# AND_4x4.net
KiCad netlist of a schematic drawn in Altium Designer
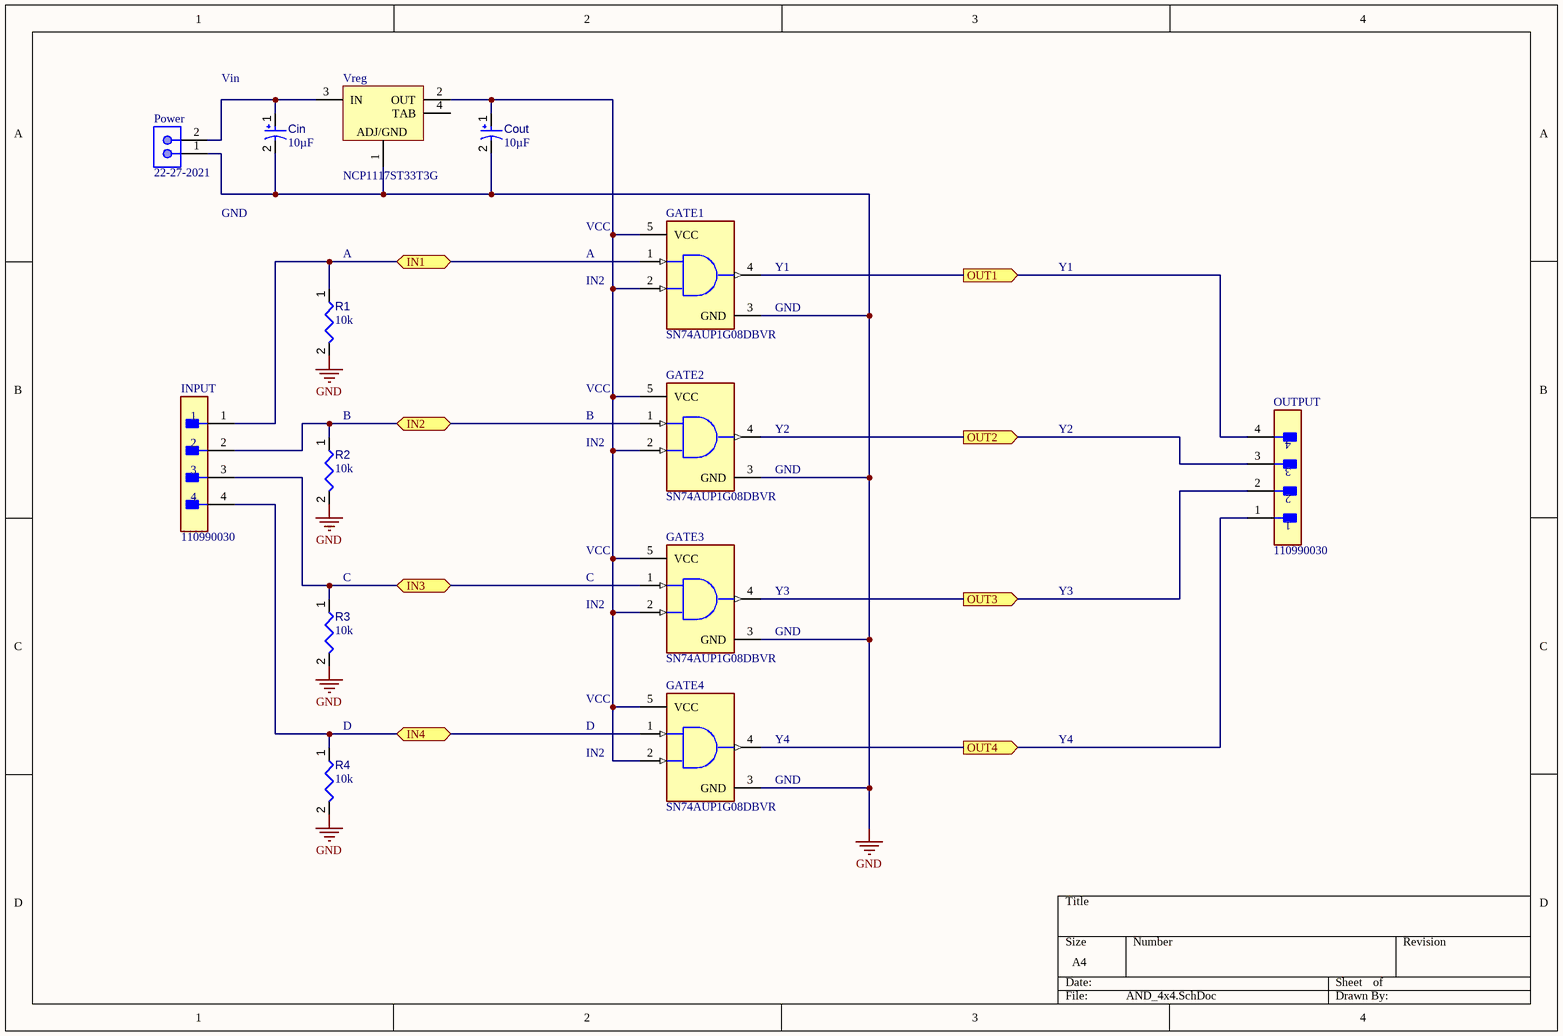
[diagram p0: AND_4x4.SchDoc]

(export (version "E")
  (design (tool "Eeschema 10.0.6"))
  (components
    (comp (ref "Cin")
      (value "10µF")
      (footprint "CAPPR55-200-1100X500X1200")
      (description "Aluminum Electrolytic Capacitor, 10 uF, +/- 20%, 50 V, -40 to 85 degC, 2-Pin THD, RoHS, Bulk")
      (fields (field (name "MANUFACTURER") "Panasonic") (field (name "TOLERANCE") "20%"))
      (libsource (lib "Varsha Sri Selvakumar") (part "CAP-P-2"))
    )
    (comp (ref "Cout")
      (value "10µF")
      (footprint "CAPPR55-200-1100X500X1200")
      (description "Aluminum Electrolytic Capacitor, 10 uF, +/- 20%, 50 V, -40 to 85 degC, 2-Pin THD, RoHS, Bulk")
      (fields (field (name "MANUFACTURER") "Panasonic") (field (name "TOLERANCE") "20%"))
      (libsource (lib "Varsha Sri Selvakumar") (part "CAP-P-2"))
    )
    (comp (ref "GATE1")
      (value "SN74AUP1G08DBVR")
      (footprint "FP-DBV0005A-IPC_C")
      (description "IC GATE AND 1CH 2-INP SOT23-5")
      (libsource (lib "Altium Content Vault") (part "17912641d453759bd3c01e445f284ed"))
    )
    (comp (ref "GATE2")
      (value "SN74AUP1G08DBVR")
      (footprint "FP-DBV0005A-IPC_C")
      (description "IC GATE AND 1CH 2-INP SOT23-5")
      (libsource (lib "Altium Content Vault") (part "17912641d453759bd3c01e445f284ed"))
    )
    (comp (ref "GATE3")
      (value "SN74AUP1G08DBVR")
      (footprint "FP-DBV0005A-IPC_C")
      (description "IC GATE AND 1CH 2-INP SOT23-5")
      (libsource (lib "Altium Content Vault") (part "17912641d453759bd3c01e445f284ed"))
    )
    (comp (ref "GATE4")
      (value "SN74AUP1G08DBVR")
      (footprint "FP-DBV0005A-IPC_C")
      (description "IC GATE AND 1CH 2-INP SOT23-5")
      (libsource (lib "Altium Content Vault") (part "17912641d453759bd3c01e445f284ed"))
    )
    (comp (ref "INPUT")
      (value "110990030")
      (footprint "FP-110990030-MFG")
      (description "GROVE 2MM 4PIN VERT CONN 10PCS")
      (libsource (lib "Altium Content Vault") (part "299a8cea1bdcbc3624fe62c390fa72c"))
    )
    (comp (ref "OUTPUT")
      (value "110990030")
      (footprint "FP-110990030-MFG")
      (description "GROVE 2MM 4PIN VERT CONN 10PCS")
      (libsource (lib "") (part "299a8cea1bdcbc3624fe62c390fa72c_1"))
    )
    (comp (ref "Power")
      (value "22-27-2021")
      (footprint "MOLX-22-27-2021_V")
      (fields (field (name "MANUFACTURER") "Molex") (field (name "PARTNUMBER") "0022272021"))
      (libsource (lib "Altium Content Vault") (part "CN-1P-M-R2"))
    )
    (comp (ref "R1")
      (value "10k")
      (footprint "RESC0402(1005)_L")
      (description "Chip Resistor, 10 kOhms, +/-1 %, 63 mW, -55 to 125 degC, 0402")
      (fields (field (name "POWER") "63mW") (field (name "TOLERANCE") "1%"))
      (libsource (lib "Varsha Sri Selvakumar") (part "RES-2"))
    )
    (comp (ref "R2")
      (value "10k")
      (footprint "RESC0402(1005)_L")
      (description "Chip Resistor, 10 kOhms, +/-1 %, 63 mW, -55 to 125 degC, 0402")
      (fields (field (name "POWER") "63mW") (field (name "TOLERANCE") "1%"))
      (libsource (lib "Varsha Sri Selvakumar") (part "RES-2"))
    )
    (comp (ref "R3")
      (value "10k")
      (footprint "RESC0402(1005)_L")
      (description "Chip Resistor, 10 kOhms, +/-1 %, 63 mW, -55 to 125 degC, 0402")
      (fields (field (name "POWER") "63mW") (field (name "TOLERANCE") "1%"))
      (libsource (lib "Varsha Sri Selvakumar") (part "RES-2"))
    )
    (comp (ref "R4")
      (value "10k")
      (footprint "RESC0402(1005)_L")
      (description "Chip Resistor, 10 kOhms, +/-1 %, 63 mW, -55 to 125 degC, 0402")
      (fields (field (name "POWER") "63mW") (field (name "TOLERANCE") "1%"))
      (libsource (lib "Varsha Sri Selvakumar") (part "RES-2"))
    )
    (comp (ref "Vreg")
      (value "NCP1117ST33T3G")
      (footprint "ONSC-SOT-223-4-318H-01_A_V")
      (fields (field (name "TOLERANCE") "1%"))
      (libsource (lib "Altium Content Vault") (part "ONSC-NCP1117-SOT223-4"))
    )
  )
  (nets
    (net (code "1") (name "/IN1") (class "Default")
      (node (ref "GATE1") (pin "1") (pinfunction "A_1") (pintype "input"))
      (node (ref "INPUT") (pin "1") (pinfunction "1_1") (pintype "passive"))
      (node (ref "R1") (pin "1") (pinfunction "1_1") (pintype "passive"))
    )
    (net (code "2") (name "/IN2") (class "Default")
      (node (ref "GATE2") (pin "1") (pinfunction "A_1") (pintype "input"))
      (node (ref "INPUT") (pin "2") (pinfunction "2_2") (pintype "passive"))
      (node (ref "R2") (pin "1") (pinfunction "1_1") (pintype "passive"))
    )
    (net (code "3") (name "/IN3") (class "Default")
      (node (ref "GATE3") (pin "1") (pinfunction "A_1") (pintype "input"))
      (node (ref "INPUT") (pin "3") (pinfunction "3_3") (pintype "passive"))
      (node (ref "R3") (pin "1") (pinfunction "1_1") (pintype "passive"))
    )
    (net (code "4") (name "/IN4") (class "Default")
      (node (ref "GATE4") (pin "1") (pinfunction "A_1") (pintype "input"))
      (node (ref "INPUT") (pin "4") (pinfunction "4_4") (pintype "passive"))
      (node (ref "R4") (pin "1") (pinfunction "1_1") (pintype "passive"))
    )
    (net (code "5") (name "/OUT1") (class "Default")
      (node (ref "GATE1") (pin "4") (pinfunction "Y_4") (pintype "output"))
      (node (ref "OUTPUT") (pin "4") (pinfunction "4_4") (pintype "passive"))
    )
    (net (code "6") (name "/OUT2") (class "Default")
      (node (ref "GATE2") (pin "4") (pinfunction "Y_4") (pintype "output"))
      (node (ref "OUTPUT") (pin "3") (pinfunction "3_3") (pintype "passive"))
    )
    (net (code "7") (name "/OUT3") (class "Default")
      (node (ref "GATE3") (pin "4") (pinfunction "Y_4") (pintype "output"))
      (node (ref "OUTPUT") (pin "2") (pinfunction "2_2") (pintype "passive"))
    )
    (net (code "8") (name "/OUT4") (class "Default")
      (node (ref "GATE4") (pin "4") (pinfunction "Y_4") (pintype "output"))
      (node (ref "OUTPUT") (pin "1") (pinfunction "1_1") (pintype "passive"))
    )
    (net (code "9") (name "GND") (class "Default")
      (node (ref "Cin") (pin "2") (pinfunction "2_2") (pintype "passive"))
      (node (ref "Cout") (pin "2") (pinfunction "2_2") (pintype "passive"))
      (node (ref "GATE1") (pin "3") (pinfunction "GND_3") (pintype "power_in"))
      (node (ref "GATE2") (pin "3") (pinfunction "GND_3") (pintype "power_in"))
      (node (ref "GATE3") (pin "3") (pinfunction "GND_3") (pintype "power_in"))
      (node (ref "GATE4") (pin "3") (pinfunction "GND_3") (pintype "power_in"))
      (node (ref "Power") (pin "1") (pinfunction "1_1") (pintype "passive"))
      (node (ref "R1") (pin "2") (pinfunction "2_2") (pintype "passive"))
      (node (ref "R2") (pin "2") (pinfunction "2_2") (pintype "passive"))
      (node (ref "R3") (pin "2") (pinfunction "2_2") (pintype "passive"))
      (node (ref "R4") (pin "2") (pinfunction "2_2") (pintype "passive"))
      (node (ref "Vreg") (pin "1") (pinfunction "ADJ/GND_1") (pintype "passive"))
    )
    (net (code "10") (name "Net-(GATE1-B)") (class "Default")
      (node (ref "Cout") (pin "1") (pinfunction "1_1") (pintype "passive"))
      (node (ref "GATE1") (pin "2") (pinfunction "B_2") (pintype "input"))
      (node (ref "GATE1") (pin "5") (pinfunction "VCC_5") (pintype "power_in"))
      (node (ref "GATE2") (pin "2") (pinfunction "B_2") (pintype "input"))
      (node (ref "GATE2") (pin "5") (pinfunction "VCC_5") (pintype "power_in"))
      (node (ref "GATE3") (pin "2") (pinfunction "B_2") (pintype "input"))
      (node (ref "GATE3") (pin "5") (pinfunction "VCC_5") (pintype "power_in"))
      (node (ref "GATE4") (pin "2") (pinfunction "B_2") (pintype "input"))
      (node (ref "GATE4") (pin "5") (pinfunction "VCC_5") (pintype "power_in"))
      (node (ref "Vreg") (pin "2") (pinfunction "OUT_2") (pintype "power_in"))
    )
    (net (code "11") (name "Net-(Vreg-IN)") (class "Default")
      (node (ref "Cin") (pin "1") (pinfunction "1_1") (pintype "passive"))
      (node (ref "Power") (pin "2") (pinfunction "2_2") (pintype "passive"))
      (node (ref "Vreg") (pin "3") (pinfunction "IN_3") (pintype "power_in"))
    )
    (net (code "12") (name "unconnected-(Vreg-TAB-Pad4)") (class "Default")
      (node (ref "Vreg") (pin "4") (pinfunction "TAB_4") (pintype "passive"))
    )
  )
)
